# Digital_Protractor_1.net
KiCad netlist of a schematic drawn in EAGLE
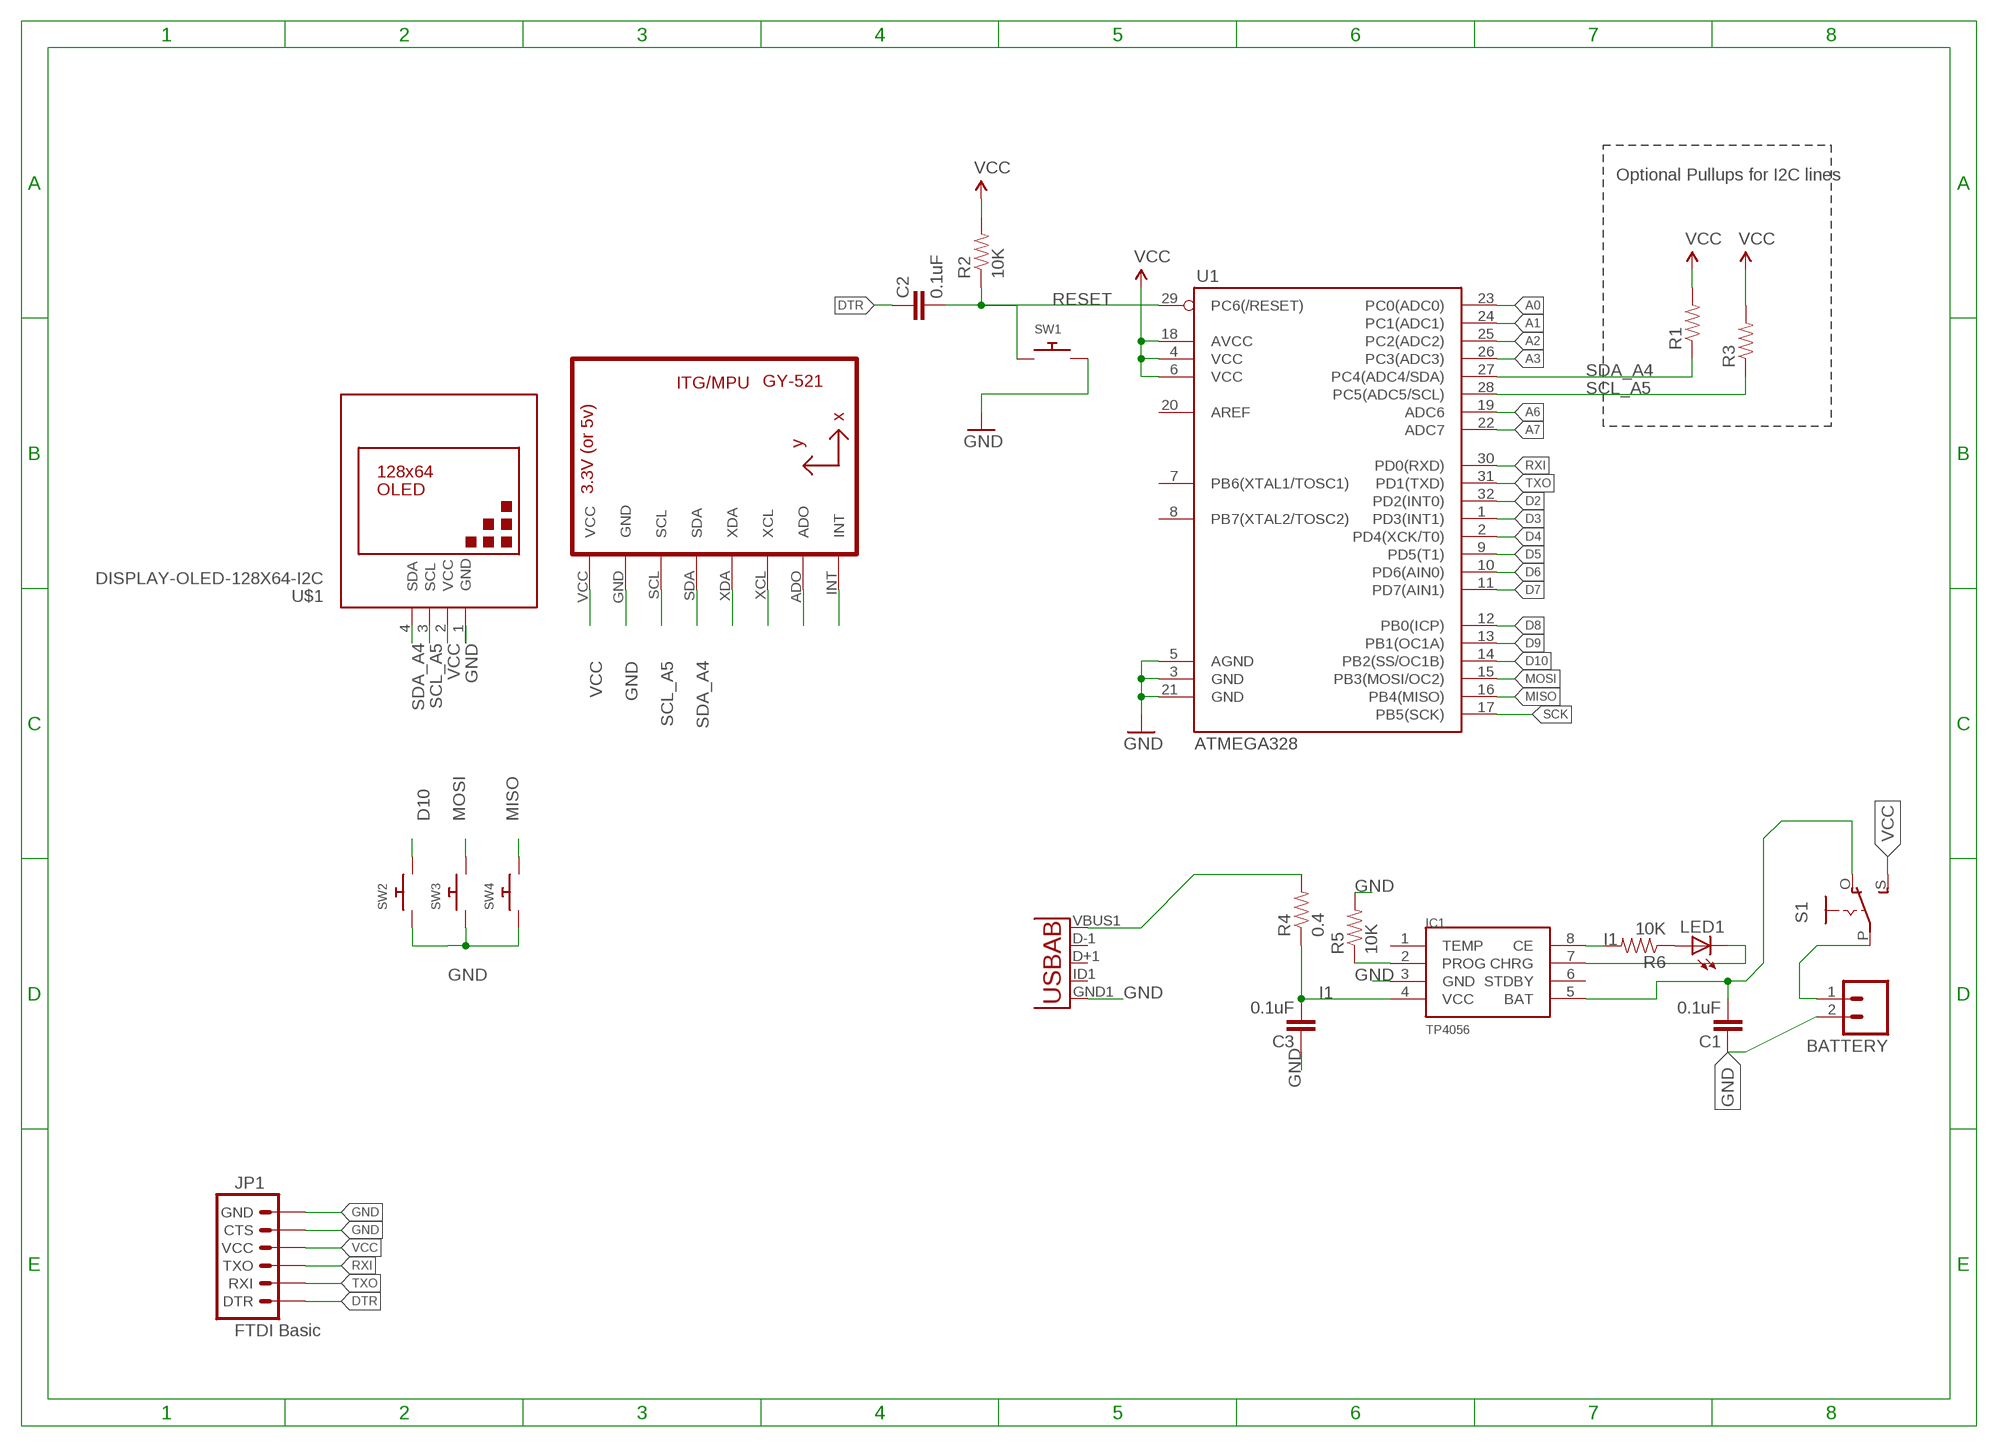
[diagram p0: schematic, sheet 1]

(export (version "E")
  (design (tool "Eeschema 10.0.6"))
  (components
    (comp (ref "BATTERY")
      (value "M02PTH")
      (footprint "eagle-import:1X02")
      (libsource (lib "eagle-import") (part "M02PTH"))
    )
    (comp (ref "C1")
      (value "0.1uF")
      (footprint "eagle-import:0603-CAP")
      (libsource (lib "eagle-import") (part "CAP0603-CAP"))
    )
    (comp (ref "C2")
      (value "0.1uF")
      (footprint "eagle-import:0603-CAP")
      (libsource (lib "eagle-import") (part "CAP0603-CAP"))
    )
    (comp (ref "C3")
      (value "0.1uF")
      (footprint "eagle-import:0603-CAP")
      (libsource (lib "eagle-import") (part "CAP0603-CAP"))
    )
    (comp (ref "IC1")
      (value "TP4056")
      (footprint "eagle-import:SOP-8")
      (libsource (lib "eagle-import") (part "TP4056"))
    )
    (comp (ref "JP1")
      (value "FTDI Basic")
      (footprint "eagle-import:1X06")
      (libsource (lib "eagle-import") (part "ARDUINO_SERIAL_PROGRAMPTH"))
    )
    (comp (ref "LED1")
      (value "LED")
      (footprint "eagle-import:SMARTLED-TTW")
      (libsource (lib "eagle-import") (part "LED"))
    )
    (comp (ref "R1")
      (value "RESISTOR0603-RES")
      (footprint "eagle-import:0603-RES")
      (libsource (lib "eagle-import") (part "RESISTOR0603-RES"))
    )
    (comp (ref "R2")
      (value "10K")
      (footprint "eagle-import:0603-RES")
      (libsource (lib "eagle-import") (part "RESISTOR0603-RES"))
    )
    (comp (ref "R3")
      (value "RESISTOR0603-RES")
      (footprint "eagle-import:0603-RES")
      (libsource (lib "eagle-import") (part "RESISTOR0603-RES"))
    )
    (comp (ref "R4")
      (value "0.4")
      (footprint "eagle-import:0603-RES")
      (libsource (lib "eagle-import") (part "RESISTOR0603-RES"))
    )
    (comp (ref "R5")
      (value "10K")
      (footprint "eagle-import:0603-RES")
      (libsource (lib "eagle-import") (part "RESISTOR0603-RES"))
    )
    (comp (ref "R6")
      (value "10K")
      (footprint "eagle-import:0603-RES")
      (libsource (lib "eagle-import") (part "RESISTOR0603-RES"))
    )
    (comp (ref "S1")
      (value "EG1218S")
      (footprint "eagle-import:EG1218")
      (libsource (lib "eagle-import") (part "EG1218S"))
    )
    (comp (ref "SW1")
      (value "SWITCH_PUSHBUTTONEVQ-PE")
      (footprint "eagle-import:TACT_PANA-EVQ")
      (libsource (lib "eagle-import") (part "SWITCH_PUSHBUTTONEVQ-PE"))
    )
    (comp (ref "SW2")
      (value "SWITCH_PUSHBUTTONSOFTTOUCHSMD_SJ")
      (footprint "eagle-import:PUSHBUTTON_SMD_SJ")
      (libsource (lib "eagle-import") (part "SWITCH_PUSHBUTTONSOFTTOUCHSMD_SJ"))
    )
    (comp (ref "SW3")
      (value "SWITCH_PUSHBUTTONSOFTTOUCHSMD_SJ")
      (footprint "eagle-import:PUSHBUTTON_SMD_SJ")
      (libsource (lib "eagle-import") (part "SWITCH_PUSHBUTTONSOFTTOUCHSMD_SJ"))
    )
    (comp (ref "SW4")
      (value "SWITCH_PUSHBUTTONSOFTTOUCHSMD_SJ")
      (footprint "eagle-import:PUSHBUTTON_SMD_SJ")
      (libsource (lib "eagle-import") (part "SWITCH_PUSHBUTTONSOFTTOUCHSMD_SJ"))
    )
    (comp (ref "U$1")
      (value "DISPLAY-OLED-128X64-I2C")
      (footprint "eagle-import:DISPLAY-OLED-128X64-I2C")
      (libsource (lib "eagle-import") (part "DISPLAY-OLED-128X64-I2C"))
    )
    (comp (ref "U1")
      (value "ATMEGA328")
      (footprint "eagle-import:TQFP32-08")
      (libsource (lib "eagle-import") (part "ATMEGA168"))
    )
    (comp (ref "U2")
      (value "GY-521MPU6050")
      (footprint "eagle-import:GY-521")
      (libsource (lib "eagle-import") (part "GY-521MPU6050"))
    )
    (comp (ref "U3")
      (value "USB\"\"")
      (footprint "eagle-import:USB-MICRO-SMD")
      (libsource (lib "eagle-import") (part "USB{dblquote}{dblquote}"))
    )
  )
  (nets
    (net (code "1") (name "/I1") (class "Default")
      (node (ref "C3") (pin "1") (pinfunction "1_1") (pintype "passive"))
      (node (ref "IC1") (pin "4") (pinfunction "VCC_4") (pintype "bidirectional"))
      (node (ref "IC1") (pin "8") (pinfunction "CE_8") (pintype "bidirectional"))
      (node (ref "R4") (pin "1") (pinfunction "1_1") (pintype "passive"))
      (node (ref "R6") (pin "2") (pinfunction "2_2") (pintype "passive"))
    )
    (net (code "2") (name "/RESET") (class "Default")
      (node (ref "C2") (pin "1") (pinfunction "1_1") (pintype "passive"))
      (node (ref "R2") (pin "1") (pinfunction "1_1") (pintype "passive"))
      (node (ref "SW1") (pin "P$1") (pinfunction "P$1_P$1") (pintype "passive"))
      (node (ref "U1") (pin "29") (pinfunction "PC6(/RESET)_29") (pintype "bidirectional"))
    )
    (net (code "3") (name "/SCL_A5") (class "Default")
      (node (ref "R3") (pin "1") (pinfunction "1_1") (pintype "passive"))
      (node (ref "U$1") (pin "3") (pinfunction "SCL_3") (pintype "bidirectional"))
      (node (ref "U1") (pin "28") (pinfunction "PC5(ADC5/SCL)_28") (pintype "bidirectional"))
      (node (ref "U2") (pin "SCL") (pinfunction "SCL_SCL") (pintype "bidirectional"))
    )
    (net (code "4") (name "/SDA_A4") (class "Default")
      (node (ref "R1") (pin "1") (pinfunction "1_1") (pintype "passive"))
      (node (ref "U$1") (pin "4") (pinfunction "SDA_4") (pintype "bidirectional"))
      (node (ref "U1") (pin "27") (pinfunction "PC4(ADC4/SDA)_27") (pintype "bidirectional"))
      (node (ref "U2") (pin "SDA") (pinfunction "SDA_SDA") (pintype "bidirectional"))
    )
    (net (code "5") (name "A0") (class "Default")
      (node (ref "U1") (pin "23") (pinfunction "PC0(ADC0)_23") (pintype "bidirectional"))
    )
    (net (code "6") (name "A1") (class "Default")
      (node (ref "U1") (pin "24") (pinfunction "PC1(ADC1)_24") (pintype "bidirectional"))
    )
    (net (code "7") (name "A2") (class "Default")
      (node (ref "U1") (pin "25") (pinfunction "PC2(ADC2)_25") (pintype "bidirectional"))
    )
    (net (code "8") (name "A3") (class "Default")
      (node (ref "U1") (pin "26") (pinfunction "PC3(ADC3)_26") (pintype "bidirectional"))
    )
    (net (code "9") (name "A6") (class "Default")
      (node (ref "U1") (pin "19") (pinfunction "ADC6_19") (pintype "bidirectional"))
    )
    (net (code "10") (name "A7") (class "Default")
      (node (ref "U1") (pin "22") (pinfunction "ADC7_22") (pintype "bidirectional"))
    )
    (net (code "11") (name "D2") (class "Default")
      (node (ref "U1") (pin "32") (pinfunction "PD2(INT0)_32") (pintype "bidirectional"))
    )
    (net (code "12") (name "D3") (class "Default")
      (node (ref "U1") (pin "1") (pinfunction "PD3(INT1)_1") (pintype "bidirectional"))
    )
    (net (code "13") (name "D4") (class "Default")
      (node (ref "U1") (pin "2") (pinfunction "PD4(XCK/T0)_2") (pintype "bidirectional"))
    )
    (net (code "14") (name "D5") (class "Default")
      (node (ref "U1") (pin "9") (pinfunction "PD5(T1)_9") (pintype "bidirectional"))
    )
    (net (code "15") (name "D6") (class "Default")
      (node (ref "U1") (pin "10") (pinfunction "PD6(AIN0)_10") (pintype "bidirectional"))
    )
    (net (code "16") (name "D7") (class "Default")
      (node (ref "U1") (pin "11") (pinfunction "PD7(AIN1)_11") (pintype "bidirectional"))
    )
    (net (code "17") (name "D8") (class "Default")
      (node (ref "U1") (pin "12") (pinfunction "PB0(ICP)_12") (pintype "bidirectional"))
    )
    (net (code "18") (name "D9") (class "Default")
      (node (ref "U1") (pin "13") (pinfunction "PB1(OC1A)_13") (pintype "bidirectional"))
    )
    (net (code "19") (name "D10") (class "Default")
      (node (ref "SW2") (pin "P$2") (pinfunction "P$2_P$2") (pintype "passive"))
      (node (ref "U1") (pin "14") (pinfunction "PB2(SS/OC1B)_14") (pintype "bidirectional"))
    )
    (net (code "20") (name "DTR") (class "Default")
      (node (ref "C2") (pin "2") (pinfunction "2_2") (pintype "passive"))
      (node (ref "JP1") (pin "1") (pinfunction "DTR_1") (pintype "passive"))
    )
    (net (code "21") (name "GND") (class "Default")
      (node (ref "BATTERY") (pin "2") (pinfunction "2_2") (pintype "passive"))
      (node (ref "C1") (pin "2") (pinfunction "2_2") (pintype "passive"))
      (node (ref "C3") (pin "2") (pinfunction "2_2") (pintype "passive"))
      (node (ref "IC1") (pin "3") (pinfunction "GND_3") (pintype "bidirectional"))
      (node (ref "JP1") (pin "5") (pinfunction "CTS_5") (pintype "passive"))
      (node (ref "JP1") (pin "6") (pinfunction "GND_6") (pintype "passive"))
      (node (ref "R5") (pin "2") (pinfunction "2_2") (pintype "passive"))
      (node (ref "SW1") (pin "P$2") (pinfunction "P$2_P$2") (pintype "passive"))
      (node (ref "SW2") (pin "P$1") (pinfunction "P$1_P$1") (pintype "passive"))
      (node (ref "SW3") (pin "P$1") (pinfunction "P$1_P$1") (pintype "passive"))
      (node (ref "SW4") (pin "P$1") (pinfunction "P$1_P$1") (pintype "passive"))
      (node (ref "U$1") (pin "1") (pinfunction "GND_1") (pintype "power_in"))
      (node (ref "U1") (pin "21") (pinfunction "GND_21") (pintype "bidirectional"))
      (node (ref "U1") (pin "3") (pinfunction "GND_3") (pintype "bidirectional"))
      (node (ref "U1") (pin "5") (pinfunction "AGND_5") (pintype "bidirectional"))
      (node (ref "U2") (pin "GND") (pinfunction "GND_GND") (pintype "bidirectional"))
      (node (ref "U3") (pin "GND1") (pinfunction "GND_GND1") (pintype "bidirectional"))
    )
    (net (code "22") (name "MISO") (class "Default")
      (node (ref "SW4") (pin "P$2") (pinfunction "P$2_P$2") (pintype "passive"))
      (node (ref "U1") (pin "16") (pinfunction "PB4(MISO)_16") (pintype "bidirectional"))
    )
    (net (code "23") (name "MOSI") (class "Default")
      (node (ref "SW3") (pin "P$2") (pinfunction "P$2_P$2") (pintype "passive"))
      (node (ref "U1") (pin "15") (pinfunction "PB3(MOSI/OC2)_15") (pintype "bidirectional"))
    )
    (net (code "24") (name "Net-(BATTERY-Pad1)") (class "Default")
      (node (ref "BATTERY") (pin "1") (pinfunction "1_1") (pintype "passive"))
      (node (ref "S1") (pin "P") (pinfunction "P_P") (pintype "passive"))
    )
    (net (code "25") (name "Net-(IC1-BAT)") (class "Default")
      (node (ref "C1") (pin "1") (pinfunction "1_1") (pintype "passive"))
      (node (ref "IC1") (pin "5") (pinfunction "BAT_5") (pintype "bidirectional"))
      (node (ref "S1") (pin "O") (pinfunction "O_O") (pintype "passive"))
    )
    (net (code "26") (name "Net-(IC1-CHRG)") (class "Default")
      (node (ref "IC1") (pin "7") (pinfunction "CHRG_7") (pintype "bidirectional"))
      (node (ref "LED1") (pin "C@1") (pinfunction "C_C@1") (pintype "passive"))
    )
    (net (code "27") (name "Net-(IC1-PROG)") (class "Default")
      (node (ref "IC1") (pin "2") (pinfunction "PROG_2") (pintype "bidirectional"))
      (node (ref "R5") (pin "1") (pinfunction "1_1") (pintype "passive"))
    )
    (net (code "28") (name "Net-(LED1-A)") (class "Default")
      (node (ref "LED1") (pin "A@1") (pinfunction "A_A@1") (pintype "passive"))
      (node (ref "R6") (pin "1") (pinfunction "1_1") (pintype "passive"))
    )
    (net (code "29") (name "Net-(U3-VBUS)") (class "Default")
      (node (ref "R4") (pin "2") (pinfunction "2_2") (pintype "passive"))
      (node (ref "U3") (pin "VBUS1") (pinfunction "VBUS_VBUS1") (pintype "bidirectional"))
    )
    (net (code "30") (name "RXI") (class "Default")
      (node (ref "JP1") (pin "3") (pinfunction "TXO_3") (pintype "passive"))
      (node (ref "U1") (pin "30") (pinfunction "PD0(RXD)_30") (pintype "bidirectional"))
    )
    (net (code "31") (name "SCK") (class "Default")
      (node (ref "U1") (pin "17") (pinfunction "PB5(SCK)_17") (pintype "bidirectional"))
    )
    (net (code "32") (name "TXO") (class "Default")
      (node (ref "JP1") (pin "2") (pinfunction "RXI_2") (pintype "passive"))
      (node (ref "U1") (pin "31") (pinfunction "PD1(TXD)_31") (pintype "bidirectional"))
    )
    (net (code "33") (name "VCC") (class "Default")
      (node (ref "JP1") (pin "4") (pinfunction "VCC_4") (pintype "passive"))
      (node (ref "R1") (pin "2") (pinfunction "2_2") (pintype "passive"))
      (node (ref "R2") (pin "2") (pinfunction "2_2") (pintype "passive"))
      (node (ref "R3") (pin "2") (pinfunction "2_2") (pintype "passive"))
      (node (ref "S1") (pin "S") (pinfunction "S_S") (pintype "passive"))
      (node (ref "U$1") (pin "2") (pinfunction "VCC_2") (pintype "power_in"))
      (node (ref "U1") (pin "18") (pinfunction "AVCC_18") (pintype "bidirectional"))
      (node (ref "U1") (pin "4") (pinfunction "VCC_4") (pintype "bidirectional"))
      (node (ref "U1") (pin "6") (pinfunction "VCC_6") (pintype "bidirectional"))
      (node (ref "U2") (pin "VCC") (pinfunction "VCC_VCC") (pintype "bidirectional"))
    )
    (net (code "34") (name "unconnected-(IC1-STDBY-Pad6)") (class "Default")
      (node (ref "IC1") (pin "6") (pinfunction "STDBY_6") (pintype "bidirectional"))
    )
    (net (code "35") (name "unconnected-(IC1-TEMP-Pad1)") (class "Default")
      (node (ref "IC1") (pin "1") (pinfunction "TEMP_1") (pintype "bidirectional"))
    )
    (net (code "36") (name "unconnected-(U1-AREF-Pad20)") (class "Default")
      (node (ref "U1") (pin "20") (pinfunction "AREF_20") (pintype "bidirectional"))
    )
    (net (code "37") (name "unconnected-(U1-PB6(XTAL1{slash}TOSC1)-Pad7)") (class "Default")
      (node (ref "U1") (pin "7") (pinfunction "PB6(XTAL1/TOSC1)_7") (pintype "bidirectional"))
    )
    (net (code "38") (name "unconnected-(U1-PB7(XTAL2{slash}TOSC2)-Pad8)") (class "Default")
      (node (ref "U1") (pin "8") (pinfunction "PB7(XTAL2/TOSC2)_8") (pintype "bidirectional"))
    )
    (net (code "39") (name "unconnected-(U2-PadADO)") (class "Default")
      (node (ref "U2") (pin "ADO") (pinfunction "ADO_ADO") (pintype "bidirectional"))
    )
    (net (code "40") (name "unconnected-(U2-PadINT)") (class "Default")
      (node (ref "U2") (pin "INT") (pinfunction "INT_INT") (pintype "bidirectional"))
    )
    (net (code "41") (name "unconnected-(U2-PadXCL)") (class "Default")
      (node (ref "U2") (pin "XCL") (pinfunction "XCL_XCL") (pintype "bidirectional"))
    )
    (net (code "42") (name "unconnected-(U2-PadXDA)") (class "Default")
      (node (ref "U2") (pin "XDA") (pinfunction "XDA_XDA") (pintype "bidirectional"))
    )
    (net (code "43") (name "unconnected-(U3-D+-PadD+1)") (class "Default")
      (node (ref "U3") (pin "D+1") (pinfunction "D+_D+1") (pintype "bidirectional"))
    )
    (net (code "44") (name "unconnected-(U3-D--PadD-1)") (class "Default")
      (node (ref "U3") (pin "D-1") (pinfunction "D-_D-1") (pintype "bidirectional"))
    )
    (net (code "45") (name "unconnected-(U3-USBID-PadID1)") (class "Default")
      (node (ref "U3") (pin "ID1") (pinfunction "USBID_ID1") (pintype "bidirectional"))
    )
  )
)
